# 7seg247.net
KiCad netlist of a schematic drawn in EAGLE
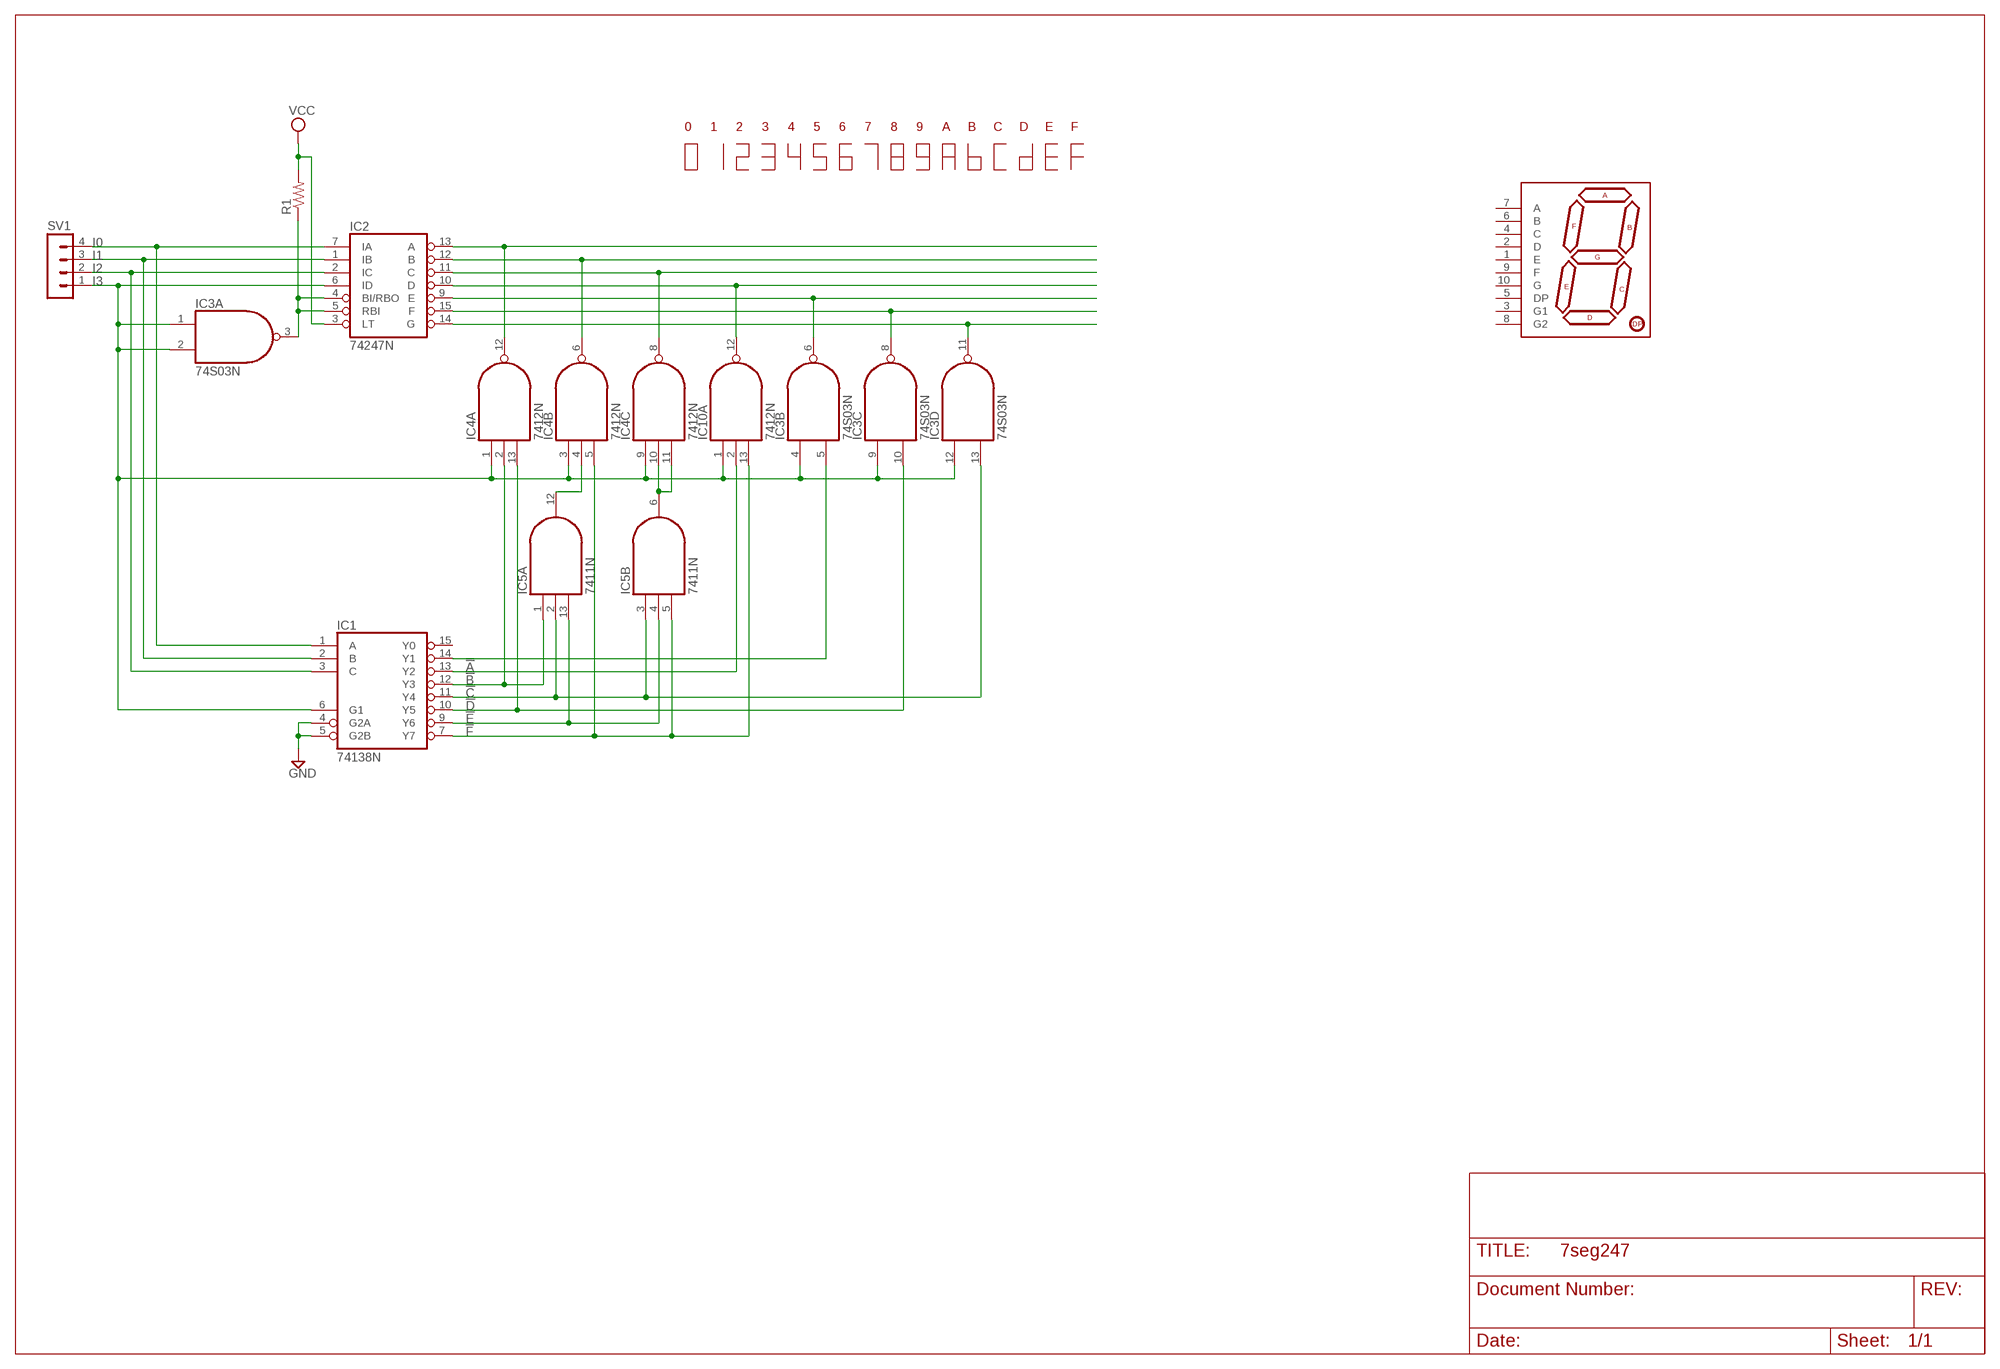
[diagram p0: schematic, sheet 1]

(export (version "E")
  (design (tool "Eeschema 10.0.6"))
  (components
    (comp (ref "IC1")
      (value "74138N")
      (footprint "eagle-import:DIL16")
      (libsource (lib "eagle-import") (part "74138NS"))
    )
    (comp (ref "IC2")
      (value "74247N")
      (footprint "eagle-import:DIL16")
      (libsource (lib "eagle-import") (part "7446N"))
    )
    (comp (ref "IC3")
      (value "74S03N")
      (footprint "eagle-import:DIL14")
      (libsource (lib "eagle-import") (part "7403NS"))
    )
    (comp (ref "IC4")
      (value "7412N")
      (footprint "eagle-import:DIL14")
      (libsource (lib "eagle-import") (part "7412N"))
    )
    (comp (ref "IC5")
      (value "7411N")
      (footprint "eagle-import:DIL14")
      (libsource (lib "eagle-import") (part "7411NS"))
    )
    (comp (ref "IC10")
      (value "7412N")
      (footprint "eagle-import:DIL14")
      (libsource (lib "eagle-import") (part "7412N"))
    )
    (comp (ref "R1")
      (value "R-US_0207/10")
      (footprint "eagle-import:0207_10")
      (libsource (lib "eagle-import") (part "R-US_0207/10"))
    )
    (comp (ref "SV1")
      (value "MA04-1")
      (footprint "eagle-import:MA04-1")
      (libsource (lib "eagle-import") (part "MA04-1"))
    )
    (comp (ref "U$1")
      (value "7-SEGMENT-DISPLAY-1\"-RED")
      (footprint "eagle-import:7-SEGMENT-1_PTH")
      (libsource (lib "eagle-import") (part "7-SEGMENT-DISPLAY-1{dblquote}-RED"))
    )
  )
  (nets
    (net (code "1") (name "/I0") (class "Default")
      (node (ref "IC1") (pin "1") (pinfunction "A_1") (pintype "input"))
      (node (ref "IC2") (pin "7") (pinfunction "IA_7") (pintype "input"))
      (node (ref "SV1") (pin "4") (pinfunction "4_4") (pintype "passive"))
    )
    (net (code "2") (name "/I1") (class "Default")
      (node (ref "IC1") (pin "2") (pinfunction "B_2") (pintype "input"))
      (node (ref "IC2") (pin "1") (pinfunction "IB_1") (pintype "input"))
      (node (ref "SV1") (pin "3") (pinfunction "3_3") (pintype "passive"))
    )
    (net (code "3") (name "/I2") (class "Default")
      (node (ref "IC1") (pin "3") (pinfunction "C_3") (pintype "input"))
      (node (ref "IC2") (pin "2") (pinfunction "IC_2") (pintype "input"))
      (node (ref "SV1") (pin "2") (pinfunction "2_2") (pintype "passive"))
    )
    (net (code "4") (name "/I3") (class "Default")
      (node (ref "IC1") (pin "6") (pinfunction "G1_6") (pintype "input"))
      (node (ref "IC10") (pin "1") (pinfunction "I0_1") (pintype "input"))
      (node (ref "IC2") (pin "6") (pinfunction "ID_6") (pintype "input"))
      (node (ref "IC3") (pin "1") (pinfunction "I0_1") (pintype "input"))
      (node (ref "IC3") (pin "12") (pinfunction "I0_12") (pintype "input"))
      (node (ref "IC3") (pin "2") (pinfunction "I1_2") (pintype "input"))
      (node (ref "IC3") (pin "4") (pinfunction "I0_4") (pintype "input"))
      (node (ref "IC3") (pin "9") (pinfunction "I0_9") (pintype "input"))
      (node (ref "IC4") (pin "1") (pinfunction "I0_1") (pintype "input"))
      (node (ref "IC4") (pin "3") (pinfunction "I0_3") (pintype "input"))
      (node (ref "IC4") (pin "9") (pinfunction "I0_9") (pintype "input"))
      (node (ref "SV1") (pin "1") (pinfunction "1_1") (pintype "passive"))
    )
    (net (code "5") (name "/~{A}") (class "Default")
      (node (ref "IC1") (pin "13") (pinfunction "Y2_13") (pintype "output"))
      (node (ref "IC10") (pin "2") (pinfunction "I1_2") (pintype "input"))
    )
    (net (code "6") (name "/~{B}") (class "Default")
      (node (ref "IC1") (pin "12") (pinfunction "Y3_12") (pintype "output"))
      (node (ref "IC4") (pin "2") (pinfunction "I1_2") (pintype "input"))
      (node (ref "IC5") (pin "1") (pinfunction "I0_1") (pintype "input"))
    )
    (net (code "7") (name "/~{C}") (class "Default")
      (node (ref "IC1") (pin "11") (pinfunction "Y4_11") (pintype "output"))
      (node (ref "IC3") (pin "13") (pinfunction "I1_13") (pintype "input"))
      (node (ref "IC5") (pin "2") (pinfunction "I1_2") (pintype "input"))
      (node (ref "IC5") (pin "3") (pinfunction "I0_3") (pintype "input"))
    )
    (net (code "8") (name "/~{D}") (class "Default")
      (node (ref "IC1") (pin "10") (pinfunction "Y5_10") (pintype "output"))
      (node (ref "IC3") (pin "10") (pinfunction "I1_10") (pintype "input"))
      (node (ref "IC4") (pin "13") (pinfunction "I2_13") (pintype "input"))
    )
    (net (code "9") (name "/~{E}") (class "Default")
      (node (ref "IC1") (pin "9") (pinfunction "Y6_9") (pintype "output"))
      (node (ref "IC5") (pin "13") (pinfunction "I2_13") (pintype "input"))
      (node (ref "IC5") (pin "4") (pinfunction "I1_4") (pintype "input"))
    )
    (net (code "10") (name "/~{F}") (class "Default")
      (node (ref "IC1") (pin "7") (pinfunction "Y7_7") (pintype "output"))
      (node (ref "IC10") (pin "13") (pinfunction "I2_13") (pintype "input"))
      (node (ref "IC4") (pin "5") (pinfunction "I2_5") (pintype "input"))
      (node (ref "IC5") (pin "5") (pinfunction "I2_5") (pintype "input"))
    )
    (net (code "11") (name "GND") (class "Default")
      (node (ref "IC1") (pin "4") (pinfunction "G2A_4") (pintype "input"))
      (node (ref "IC1") (pin "5") (pinfunction "G2B_5") (pintype "input"))
    )
    (net (code "12") (name "Net-(IC1A-Y1)") (class "Default")
      (node (ref "IC1") (pin "14") (pinfunction "Y1_14") (pintype "output"))
      (node (ref "IC3") (pin "5") (pinfunction "I1_5") (pintype "input"))
    )
    (net (code "13") (name "Net-(IC2A-A)") (class "Default")
      (node (ref "IC2") (pin "13") (pinfunction "A_13") (pintype "open_collector"))
      (node (ref "IC4") (pin "12") (pinfunction "O_12") (pintype "open_collector"))
    )
    (net (code "14") (name "Net-(IC2A-B)") (class "Default")
      (node (ref "IC2") (pin "12") (pinfunction "B_12") (pintype "open_collector"))
      (node (ref "IC4") (pin "6") (pinfunction "O_6") (pintype "open_collector"))
    )
    (net (code "15") (name "Net-(IC2A-BI{slash}RBO)") (class "Default")
      (node (ref "IC2") (pin "4") (pinfunction "BI/RBO_4") (pintype "input"))
      (node (ref "IC2") (pin "5") (pinfunction "RBI_5") (pintype "input"))
      (node (ref "IC3") (pin "3") (pinfunction "O_3") (pintype "open_collector"))
      (node (ref "R1") (pin "1") (pinfunction "1_1") (pintype "passive"))
    )
    (net (code "16") (name "Net-(IC2A-C)") (class "Default")
      (node (ref "IC2") (pin "11") (pinfunction "C_11") (pintype "open_collector"))
      (node (ref "IC4") (pin "8") (pinfunction "O_8") (pintype "open_collector"))
    )
    (net (code "17") (name "Net-(IC2A-E)") (class "Default")
      (node (ref "IC2") (pin "9") (pinfunction "E_9") (pintype "open_collector"))
      (node (ref "IC3") (pin "6") (pinfunction "O_6") (pintype "open_collector"))
    )
    (net (code "18") (name "Net-(IC2A-F)") (class "Default")
      (node (ref "IC2") (pin "15") (pinfunction "F_15") (pintype "open_collector"))
      (node (ref "IC3") (pin "8") (pinfunction "O_8") (pintype "open_collector"))
    )
    (net (code "19") (name "Net-(IC2A-G)") (class "Default")
      (node (ref "IC2") (pin "14") (pinfunction "G_14") (pintype "open_collector"))
      (node (ref "IC3") (pin "11") (pinfunction "O_11") (pintype "open_collector"))
    )
    (net (code "20") (name "Net-(IC4B-I1)") (class "Default")
      (node (ref "IC4") (pin "4") (pinfunction "I1_4") (pintype "input"))
      (node (ref "IC5") (pin "12") (pinfunction "O_12") (pintype "output"))
    )
    (net (code "21") (name "Net-(IC4C-I1)") (class "Default")
      (node (ref "IC4") (pin "10") (pinfunction "I1_10") (pintype "input"))
      (node (ref "IC4") (pin "11") (pinfunction "I2_11") (pintype "input"))
      (node (ref "IC5") (pin "6") (pinfunction "O_6") (pintype "output"))
    )
    (net (code "22") (name "Net-(IC10A-O)") (class "Default")
      (node (ref "IC10") (pin "12") (pinfunction "O_12") (pintype "open_collector"))
      (node (ref "IC2") (pin "10") (pinfunction "D_10") (pintype "open_collector"))
    )
    (net (code "23") (name "VCC") (class "Default")
      (node (ref "IC2") (pin "3") (pinfunction "LT_3") (pintype "input"))
      (node (ref "R1") (pin "2") (pinfunction "2_2") (pintype "passive"))
    )
    (net (code "24") (name "unconnected-(IC1A-Y0-Pad15)") (class "Default")
      (node (ref "IC1") (pin "15") (pinfunction "Y0_15") (pintype "output"))
    )
    (net (code "25") (name "unconnected-(U$1-A-Pad7)") (class "Default")
      (node (ref "U$1") (pin "7") (pinfunction "A_7") (pintype "bidirectional"))
    )
    (net (code "26") (name "unconnected-(U$1-B-Pad6)") (class "Default")
      (node (ref "U$1") (pin "6") (pinfunction "B_6") (pintype "bidirectional"))
    )
    (net (code "27") (name "unconnected-(U$1-C-Pad4)") (class "Default")
      (node (ref "U$1") (pin "4") (pinfunction "C_4") (pintype "bidirectional"))
    )
    (net (code "28") (name "unconnected-(U$1-D-Pad2)") (class "Default")
      (node (ref "U$1") (pin "2") (pinfunction "D_2") (pintype "bidirectional"))
    )
    (net (code "29") (name "unconnected-(U$1-DP-Pad5)") (class "Default")
      (node (ref "U$1") (pin "5") (pinfunction "DP_5") (pintype "bidirectional"))
    )
    (net (code "30") (name "unconnected-(U$1-E-Pad1)") (class "Default")
      (node (ref "U$1") (pin "1") (pinfunction "E_1") (pintype "bidirectional"))
    )
    (net (code "31") (name "unconnected-(U$1-F-Pad9)") (class "Default")
      (node (ref "U$1") (pin "9") (pinfunction "F_9") (pintype "bidirectional"))
    )
    (net (code "32") (name "unconnected-(U$1-G-Pad10)") (class "Default")
      (node (ref "U$1") (pin "10") (pinfunction "G_10") (pintype "bidirectional"))
    )
    (net (code "33") (name "unconnected-(U$1-G1-Pad3)") (class "Default")
      (node (ref "U$1") (pin "3") (pinfunction "G1_3") (pintype "bidirectional"))
    )
    (net (code "34") (name "unconnected-(U$1-G2-Pad8)") (class "Default")
      (node (ref "U$1") (pin "8") (pinfunction "G2_8") (pintype "bidirectional"))
    )
  )
)
